# esparducam.net
KiCad netlist of a schematic drawn in EAGLE
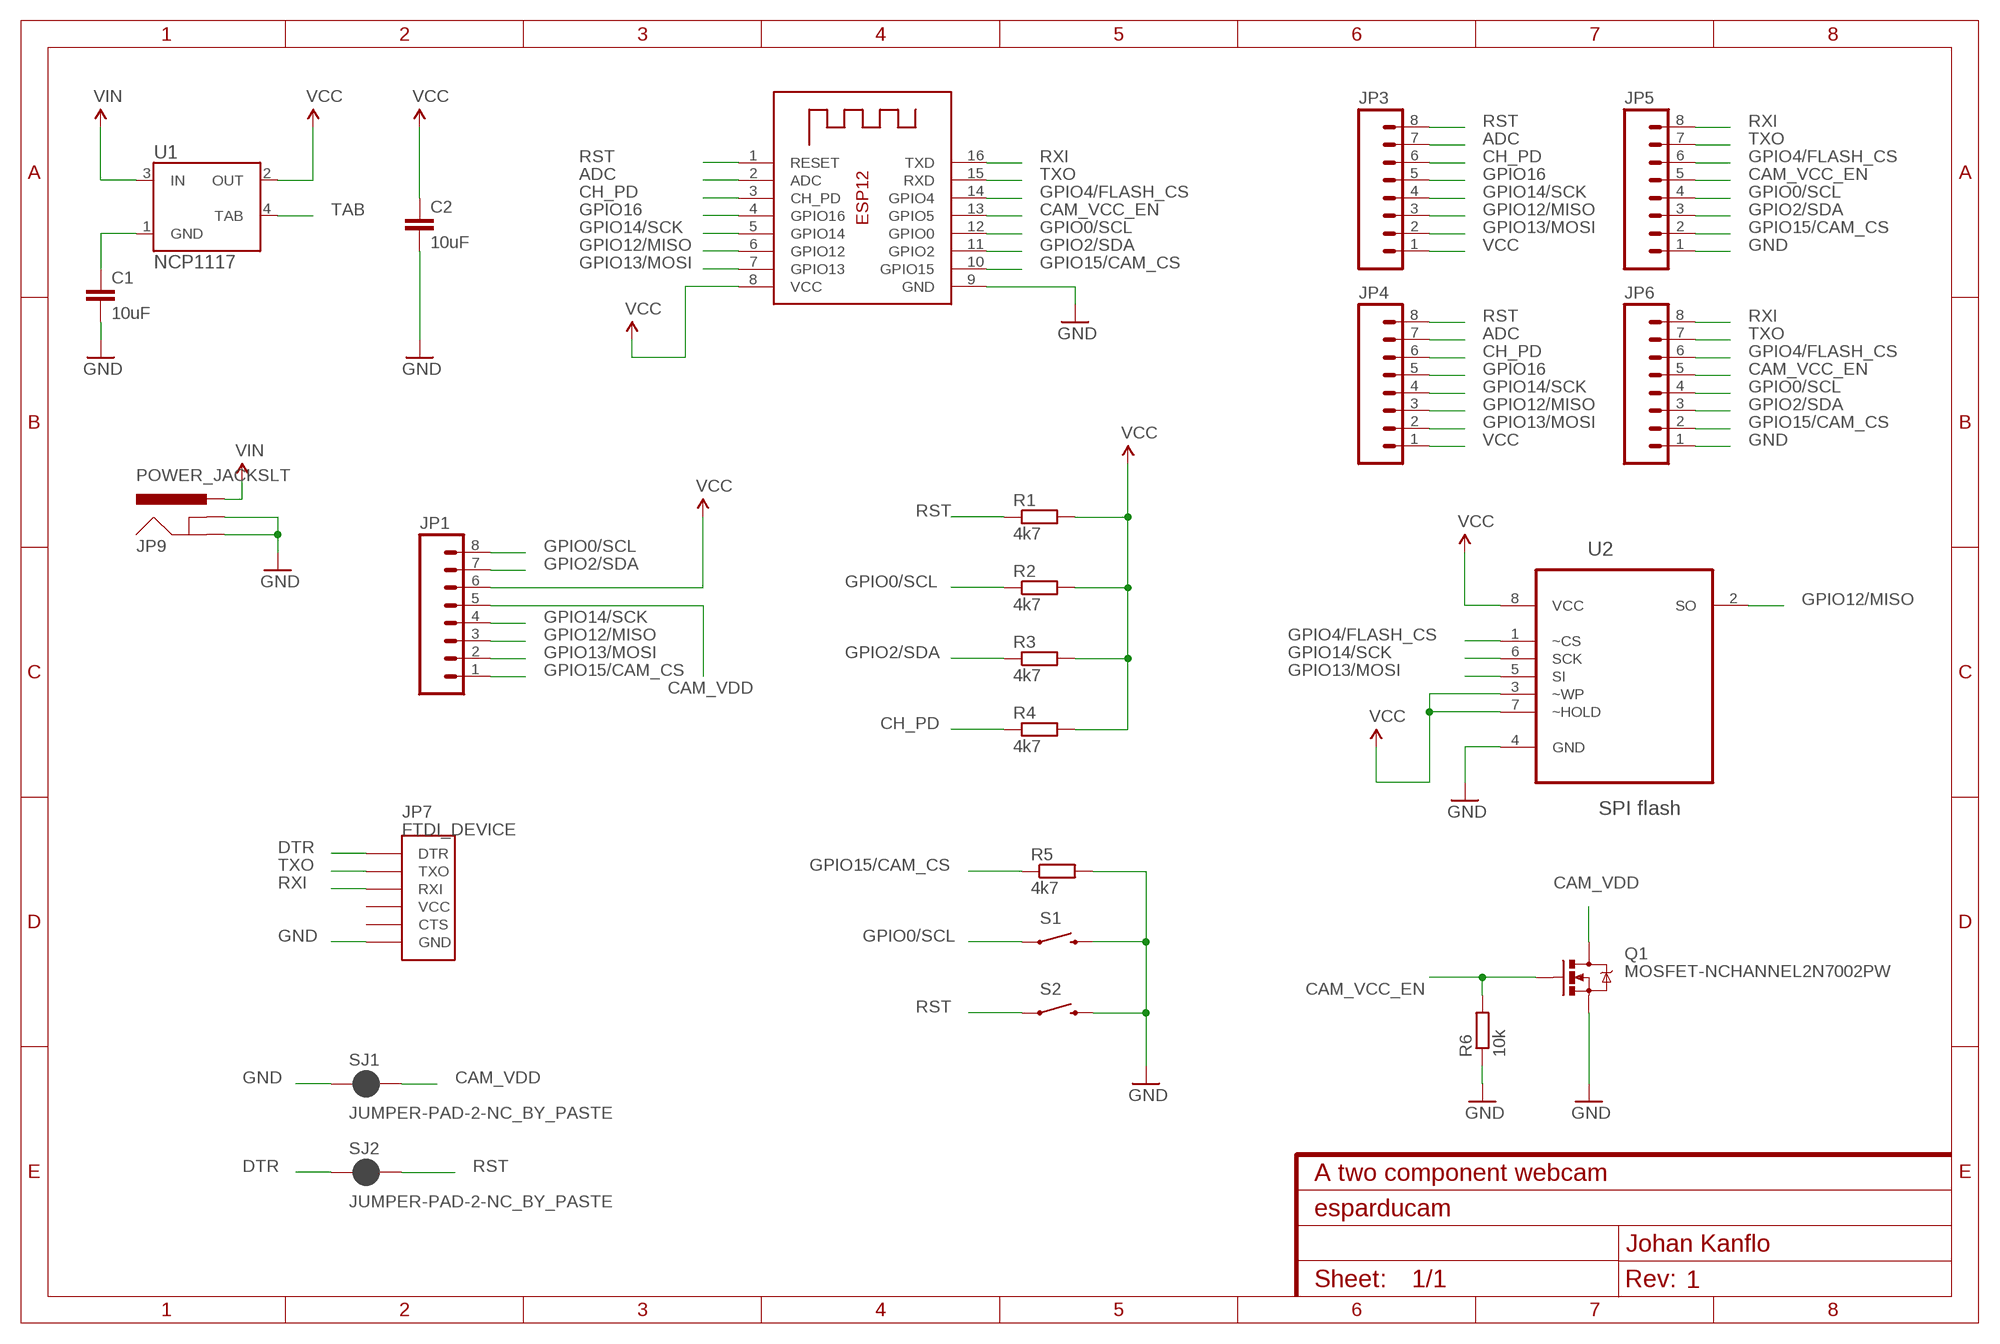
[diagram p0: schematic, sheet 1]

(export (version "E")
  (design (tool "Eeschema 10.0.6"))
  (components
    (comp (ref "C1")
      (value "10uF")
      (footprint "eagle-import:0603-CAP")
      (libsource (lib "eagle-import") (part "CAP0603-CAP"))
    )
    (comp (ref "C2")
      (value "10uF")
      (footprint "eagle-import:0603-CAP")
      (libsource (lib "eagle-import") (part "CAP0603-CAP"))
    )
    (comp (ref "JP1")
      (value "M08")
      (footprint "eagle-import:1X08_ROUND")
      (libsource (lib "eagle-import") (part "M08"))
    )
    (comp (ref "JP3")
      (value "M08")
      (footprint "eagle-import:1X08_ROUND")
      (libsource (lib "eagle-import") (part "M08"))
    )
    (comp (ref "JP4")
      (value "M08")
      (footprint "eagle-import:1X08_ROUND")
      (libsource (lib "eagle-import") (part "M08"))
    )
    (comp (ref "JP5")
      (value "M08")
      (footprint "eagle-import:1X08_ROUND")
      (libsource (lib "eagle-import") (part "M08"))
    )
    (comp (ref "JP6")
      (value "M08")
      (footprint "eagle-import:1X08_ROUND")
      (libsource (lib "eagle-import") (part "M08"))
    )
    (comp (ref "JP7")
      (value "FTDI_DEVICE")
      (footprint "eagle-import:FTDI_DEVICE_SIDE")
      (libsource (lib "eagle-import") (part "FTDI_DEVICE"))
    )
    (comp (ref "JP9")
      (value "POWER_JACKSLT")
      (footprint "eagle-import:POWER_JACK_SLOT")
      (libsource (lib "eagle-import") (part "POWER_JACKSLT"))
    )
    (comp (ref "Q1")
      (value "MOSFET-NCHANNEL2N7002PW")
      (footprint "eagle-import:SOT323")
      (libsource (lib "eagle-import") (part "MOSFET-NCHANNEL2N7002PW"))
    )
    (comp (ref "R1")
      (value "4k7")
      (footprint "eagle-import:R0603")
      (libsource (lib "eagle-import") (part "R-EU_R0603"))
    )
    (comp (ref "R2")
      (value "4k7")
      (footprint "eagle-import:R0603")
      (libsource (lib "eagle-import") (part "R-EU_R0603"))
    )
    (comp (ref "R3")
      (value "4k7")
      (footprint "eagle-import:R0603")
      (libsource (lib "eagle-import") (part "R-EU_R0603"))
    )
    (comp (ref "R4")
      (value "4k7")
      (footprint "eagle-import:R0603")
      (libsource (lib "eagle-import") (part "R-EU_R0603"))
    )
    (comp (ref "R5")
      (value "4k7")
      (footprint "eagle-import:R0603")
      (libsource (lib "eagle-import") (part "R-EU_R0603"))
    )
    (comp (ref "R6")
      (value "10k")
      (footprint "eagle-import:R0603")
      (libsource (lib "eagle-import") (part "R-EU_R0603"))
    )
    (comp (ref "S1")
      (value "SWITCH-MOMENTARY-2SMD-1101NE")
      (footprint "eagle-import:TACTILE-SWITCH-1101NE")
      (libsource (lib "eagle-import") (part "SWITCH-MOMENTARY-2SMD-1101NE"))
    )
    (comp (ref "S2")
      (value "SWITCH-MOMENTARY-2SMD-1101NE")
      (footprint "eagle-import:TACTILE-SWITCH-1101NE")
      (libsource (lib "eagle-import") (part "SWITCH-MOMENTARY-2SMD-1101NE"))
    )
    (comp (ref "SJ1")
      (value "JUMPER-PAD-2-NC_BY_PASTE")
      (footprint "eagle-import:PAD-JUMPER-2-NC_BY_PASTE_YES_SILK")
      (libsource (lib "eagle-import") (part "JUMPER-PAD-2-NC_BY_PASTE"))
    )
    (comp (ref "SJ2")
      (value "JUMPER-PAD-2-NC_BY_PASTE")
      (footprint "eagle-import:PAD-JUMPER-2-NC_BY_PASTE_YES_SILK")
      (libsource (lib "eagle-import") (part "JUMPER-PAD-2-NC_BY_PASTE"))
    )
    (comp (ref "U1")
      (value "NCP1117")
      (footprint "eagle-import:SOT223")
      (libsource (lib "eagle-import") (part "NCP1117"))
    )
    (comp (ref "U2")
      (value "SPI flash")
      (footprint "eagle-import:SOIC127P600X175-8N")
      (fields (field (name "MPN") "AT25DF021-SSH-B"))
      (libsource (lib "eagle-import") (part "AT25DF021-SSH-B"))
    )
    (comp (ref "X1")
      (value "ESP-12")
      (footprint "eagle-import:ESP-12")
      (libsource (lib "eagle-import") (part "ESP-12"))
    )
  )
  (nets
    (net (code "1") (name "/ADC") (class "Default")
      (node (ref "JP3") (pin "7") (pinfunction "7_7") (pintype "passive"))
      (node (ref "JP4") (pin "7") (pinfunction "7_7") (pintype "passive"))
      (node (ref "X1") (pin "2") (pinfunction "ADC_2") (pintype "passive"))
    )
    (net (code "2") (name "/CAM_VCC_EN") (class "Default")
      (node (ref "JP5") (pin "5") (pinfunction "5_5") (pintype "passive"))
      (node (ref "JP6") (pin "5") (pinfunction "5_5") (pintype "passive"))
      (node (ref "Q1") (pin "1") (pinfunction "G_1") (pintype "passive"))
      (node (ref "R6") (pin "2") (pinfunction "2_2") (pintype "passive"))
      (node (ref "X1") (pin "13") (pinfunction "GPIO5_13") (pintype "bidirectional"))
    )
    (net (code "3") (name "/CAM_VDD") (class "Default")
      (node (ref "JP1") (pin "5") (pinfunction "5_5") (pintype "passive"))
      (node (ref "Q1") (pin "3") (pinfunction "D_3") (pintype "passive"))
      (node (ref "SJ1") (pin "2") (pinfunction "2_2") (pintype "passive"))
    )
    (net (code "4") (name "/CH_PD") (class "Default")
      (node (ref "JP3") (pin "6") (pinfunction "6_6") (pintype "passive"))
      (node (ref "JP4") (pin "6") (pinfunction "6_6") (pintype "passive"))
      (node (ref "R4") (pin "1") (pinfunction "1_1") (pintype "passive"))
      (node (ref "X1") (pin "3") (pinfunction "CH_PD_3") (pintype "input"))
    )
    (net (code "5") (name "/DTR") (class "Default")
      (node (ref "JP7") (pin "P$1") (pinfunction "DTR_P$1") (pintype "bidirectional"))
      (node (ref "SJ2") (pin "1") (pinfunction "1_1") (pintype "passive"))
    )
    (net (code "6") (name "/GPIO0{slash}SCL") (class "Default")
      (node (ref "JP1") (pin "8") (pinfunction "8_8") (pintype "passive"))
      (node (ref "JP5") (pin "4") (pinfunction "4_4") (pintype "passive"))
      (node (ref "JP6") (pin "4") (pinfunction "4_4") (pintype "passive"))
      (node (ref "R2") (pin "1") (pinfunction "1_1") (pintype "passive"))
      (node (ref "S1") (pin "1") (pinfunction "1_1") (pintype "passive"))
      (node (ref "X1") (pin "12") (pinfunction "GPIO0_12") (pintype "bidirectional"))
    )
    (net (code "7") (name "/GPIO2{slash}SDA") (class "Default")
      (node (ref "JP1") (pin "7") (pinfunction "7_7") (pintype "passive"))
      (node (ref "JP5") (pin "3") (pinfunction "3_3") (pintype "passive"))
      (node (ref "JP6") (pin "3") (pinfunction "3_3") (pintype "passive"))
      (node (ref "R3") (pin "1") (pinfunction "1_1") (pintype "passive"))
      (node (ref "X1") (pin "11") (pinfunction "GPIO2_11") (pintype "bidirectional"))
    )
    (net (code "8") (name "/GPIO4{slash}FLASH_CS") (class "Default")
      (node (ref "JP5") (pin "6") (pinfunction "6_6") (pintype "passive"))
      (node (ref "JP6") (pin "6") (pinfunction "6_6") (pintype "passive"))
      (node (ref "U2") (pin "1") (pinfunction "~{CS}_1") (pintype "input"))
      (node (ref "X1") (pin "14") (pinfunction "GPIO4_14") (pintype "bidirectional"))
    )
    (net (code "9") (name "/GPIO12{slash}MISO") (class "Default")
      (node (ref "JP1") (pin "3") (pinfunction "3_3") (pintype "passive"))
      (node (ref "JP3") (pin "3") (pinfunction "3_3") (pintype "passive"))
      (node (ref "JP4") (pin "3") (pinfunction "3_3") (pintype "passive"))
      (node (ref "U2") (pin "2") (pinfunction "SO_2") (pintype "output"))
      (node (ref "X1") (pin "6") (pinfunction "GPIO12_6") (pintype "bidirectional"))
    )
    (net (code "10") (name "/GPIO13{slash}MOSI") (class "Default")
      (node (ref "JP1") (pin "2") (pinfunction "2_2") (pintype "passive"))
      (node (ref "JP3") (pin "2") (pinfunction "2_2") (pintype "passive"))
      (node (ref "JP4") (pin "2") (pinfunction "2_2") (pintype "passive"))
      (node (ref "U2") (pin "5") (pinfunction "SI_5") (pintype "input"))
      (node (ref "X1") (pin "7") (pinfunction "GPIO13_7") (pintype "bidirectional"))
    )
    (net (code "11") (name "/GPIO14{slash}SCK") (class "Default")
      (node (ref "JP1") (pin "4") (pinfunction "4_4") (pintype "passive"))
      (node (ref "JP3") (pin "4") (pinfunction "4_4") (pintype "passive"))
      (node (ref "JP4") (pin "4") (pinfunction "4_4") (pintype "passive"))
      (node (ref "U2") (pin "6") (pinfunction "SCK_6") (pintype "input"))
      (node (ref "X1") (pin "5") (pinfunction "GPIO14_5") (pintype "bidirectional"))
    )
    (net (code "12") (name "/GPIO15{slash}CAM_CS") (class "Default")
      (node (ref "JP1") (pin "1") (pinfunction "1_1") (pintype "passive"))
      (node (ref "JP5") (pin "2") (pinfunction "2_2") (pintype "passive"))
      (node (ref "JP6") (pin "2") (pinfunction "2_2") (pintype "passive"))
      (node (ref "R5") (pin "1") (pinfunction "1_1") (pintype "passive"))
      (node (ref "X1") (pin "10") (pinfunction "GPIO15_10") (pintype "bidirectional"))
    )
    (net (code "13") (name "/GPIO16") (class "Default")
      (node (ref "JP3") (pin "5") (pinfunction "5_5") (pintype "passive"))
      (node (ref "JP4") (pin "5") (pinfunction "5_5") (pintype "passive"))
      (node (ref "X1") (pin "4") (pinfunction "GPIO16_4") (pintype "bidirectional"))
    )
    (net (code "14") (name "/RST") (class "Default")
      (node (ref "JP3") (pin "8") (pinfunction "8_8") (pintype "passive"))
      (node (ref "JP4") (pin "8") (pinfunction "8_8") (pintype "passive"))
      (node (ref "R1") (pin "1") (pinfunction "1_1") (pintype "passive"))
      (node (ref "S2") (pin "1") (pinfunction "1_1") (pintype "passive"))
      (node (ref "SJ2") (pin "2") (pinfunction "2_2") (pintype "passive"))
      (node (ref "X1") (pin "1") (pinfunction "RESET_1") (pintype "input"))
    )
    (net (code "15") (name "/RXI") (class "Default")
      (node (ref "JP5") (pin "8") (pinfunction "8_8") (pintype "passive"))
      (node (ref "JP6") (pin "8") (pinfunction "8_8") (pintype "passive"))
      (node (ref "JP7") (pin "P$3") (pinfunction "RXI_P$3") (pintype "bidirectional"))
      (node (ref "X1") (pin "16") (pinfunction "TXD_16") (pintype "output"))
    )
    (net (code "16") (name "/TAB") (class "Default")
      (node (ref "U1") (pin "4") (pinfunction "TAB_4") (pintype "bidirectional"))
    )
    (net (code "17") (name "/TXO") (class "Default")
      (node (ref "JP5") (pin "7") (pinfunction "7_7") (pintype "passive"))
      (node (ref "JP6") (pin "7") (pinfunction "7_7") (pintype "passive"))
      (node (ref "JP7") (pin "P$2") (pinfunction "TXO_P$2") (pintype "bidirectional"))
      (node (ref "X1") (pin "15") (pinfunction "RXD_15") (pintype "input"))
    )
    (net (code "18") (name "GND") (class "Default")
      (node (ref "C1") (pin "2") (pinfunction "2_2") (pintype "passive"))
      (node (ref "C2") (pin "2") (pinfunction "2_2") (pintype "passive"))
      (node (ref "JP5") (pin "1") (pinfunction "1_1") (pintype "passive"))
      (node (ref "JP6") (pin "1") (pinfunction "1_1") (pintype "passive"))
      (node (ref "JP7") (pin "P$6") (pinfunction "GND_P$6") (pintype "bidirectional"))
      (node (ref "JP9") (pin "GND@1") (pinfunction "GNDBREAK_GND@1") (pintype "bidirectional"))
      (node (ref "JP9") (pin "GND@2") (pinfunction "GND_GND@2") (pintype "bidirectional"))
      (node (ref "Q1") (pin "2") (pinfunction "S_2") (pintype "passive"))
      (node (ref "R5") (pin "2") (pinfunction "2_2") (pintype "passive"))
      (node (ref "R6") (pin "1") (pinfunction "1_1") (pintype "passive"))
      (node (ref "S1") (pin "2") (pinfunction "2_2") (pintype "passive"))
      (node (ref "S2") (pin "2") (pinfunction "2_2") (pintype "passive"))
      (node (ref "SJ1") (pin "1") (pinfunction "1_1") (pintype "passive"))
      (node (ref "U2") (pin "4") (pinfunction "GND_4") (pintype "passive"))
      (node (ref "X1") (pin "9") (pinfunction "GND_9") (pintype "power_in"))
    )
    (net (code "19") (name "Net-(U1-GND)") (class "Default")
      (node (ref "C1") (pin "1") (pinfunction "1_1") (pintype "passive"))
      (node (ref "U1") (pin "1") (pinfunction "GND_1") (pintype "bidirectional"))
    )
    (net (code "20") (name "VCC") (class "Default")
      (node (ref "C2") (pin "1") (pinfunction "1_1") (pintype "passive"))
      (node (ref "JP1") (pin "6") (pinfunction "6_6") (pintype "passive"))
      (node (ref "JP3") (pin "1") (pinfunction "1_1") (pintype "passive"))
      (node (ref "JP4") (pin "1") (pinfunction "1_1") (pintype "passive"))
      (node (ref "R1") (pin "2") (pinfunction "2_2") (pintype "passive"))
      (node (ref "R2") (pin "2") (pinfunction "2_2") (pintype "passive"))
      (node (ref "R3") (pin "2") (pinfunction "2_2") (pintype "passive"))
      (node (ref "R4") (pin "2") (pinfunction "2_2") (pintype "passive"))
      (node (ref "U1") (pin "2") (pinfunction "OUT_2") (pintype "bidirectional"))
      (node (ref "U2") (pin "3") (pinfunction "~{WP}_3") (pintype "input"))
      (node (ref "U2") (pin "7") (pinfunction "~{HOLD}_7") (pintype "input"))
      (node (ref "U2") (pin "8") (pinfunction "VCC_8") (pintype "power_in"))
      (node (ref "X1") (pin "8") (pinfunction "VCC_8") (pintype "power_in"))
    )
    (net (code "21") (name "VIN") (class "Default")
      (node (ref "JP9") (pin "PWR") (pinfunction "PWR_PWR") (pintype "bidirectional"))
      (node (ref "U1") (pin "3") (pinfunction "IN_3") (pintype "bidirectional"))
    )
    (net (code "22") (name "unconnected-(JP7-CTS-PadP$5)") (class "Default")
      (node (ref "JP7") (pin "P$5") (pinfunction "CTS_P$5") (pintype "bidirectional"))
    )
    (net (code "23") (name "unconnected-(JP7-VCC-PadP$4)") (class "Default")
      (node (ref "JP7") (pin "P$4") (pinfunction "VCC_P$4") (pintype "bidirectional"))
    )
  )
)
